# pc_sensything_v1_4.net
KiCad netlist of a schematic drawn in EAGLE
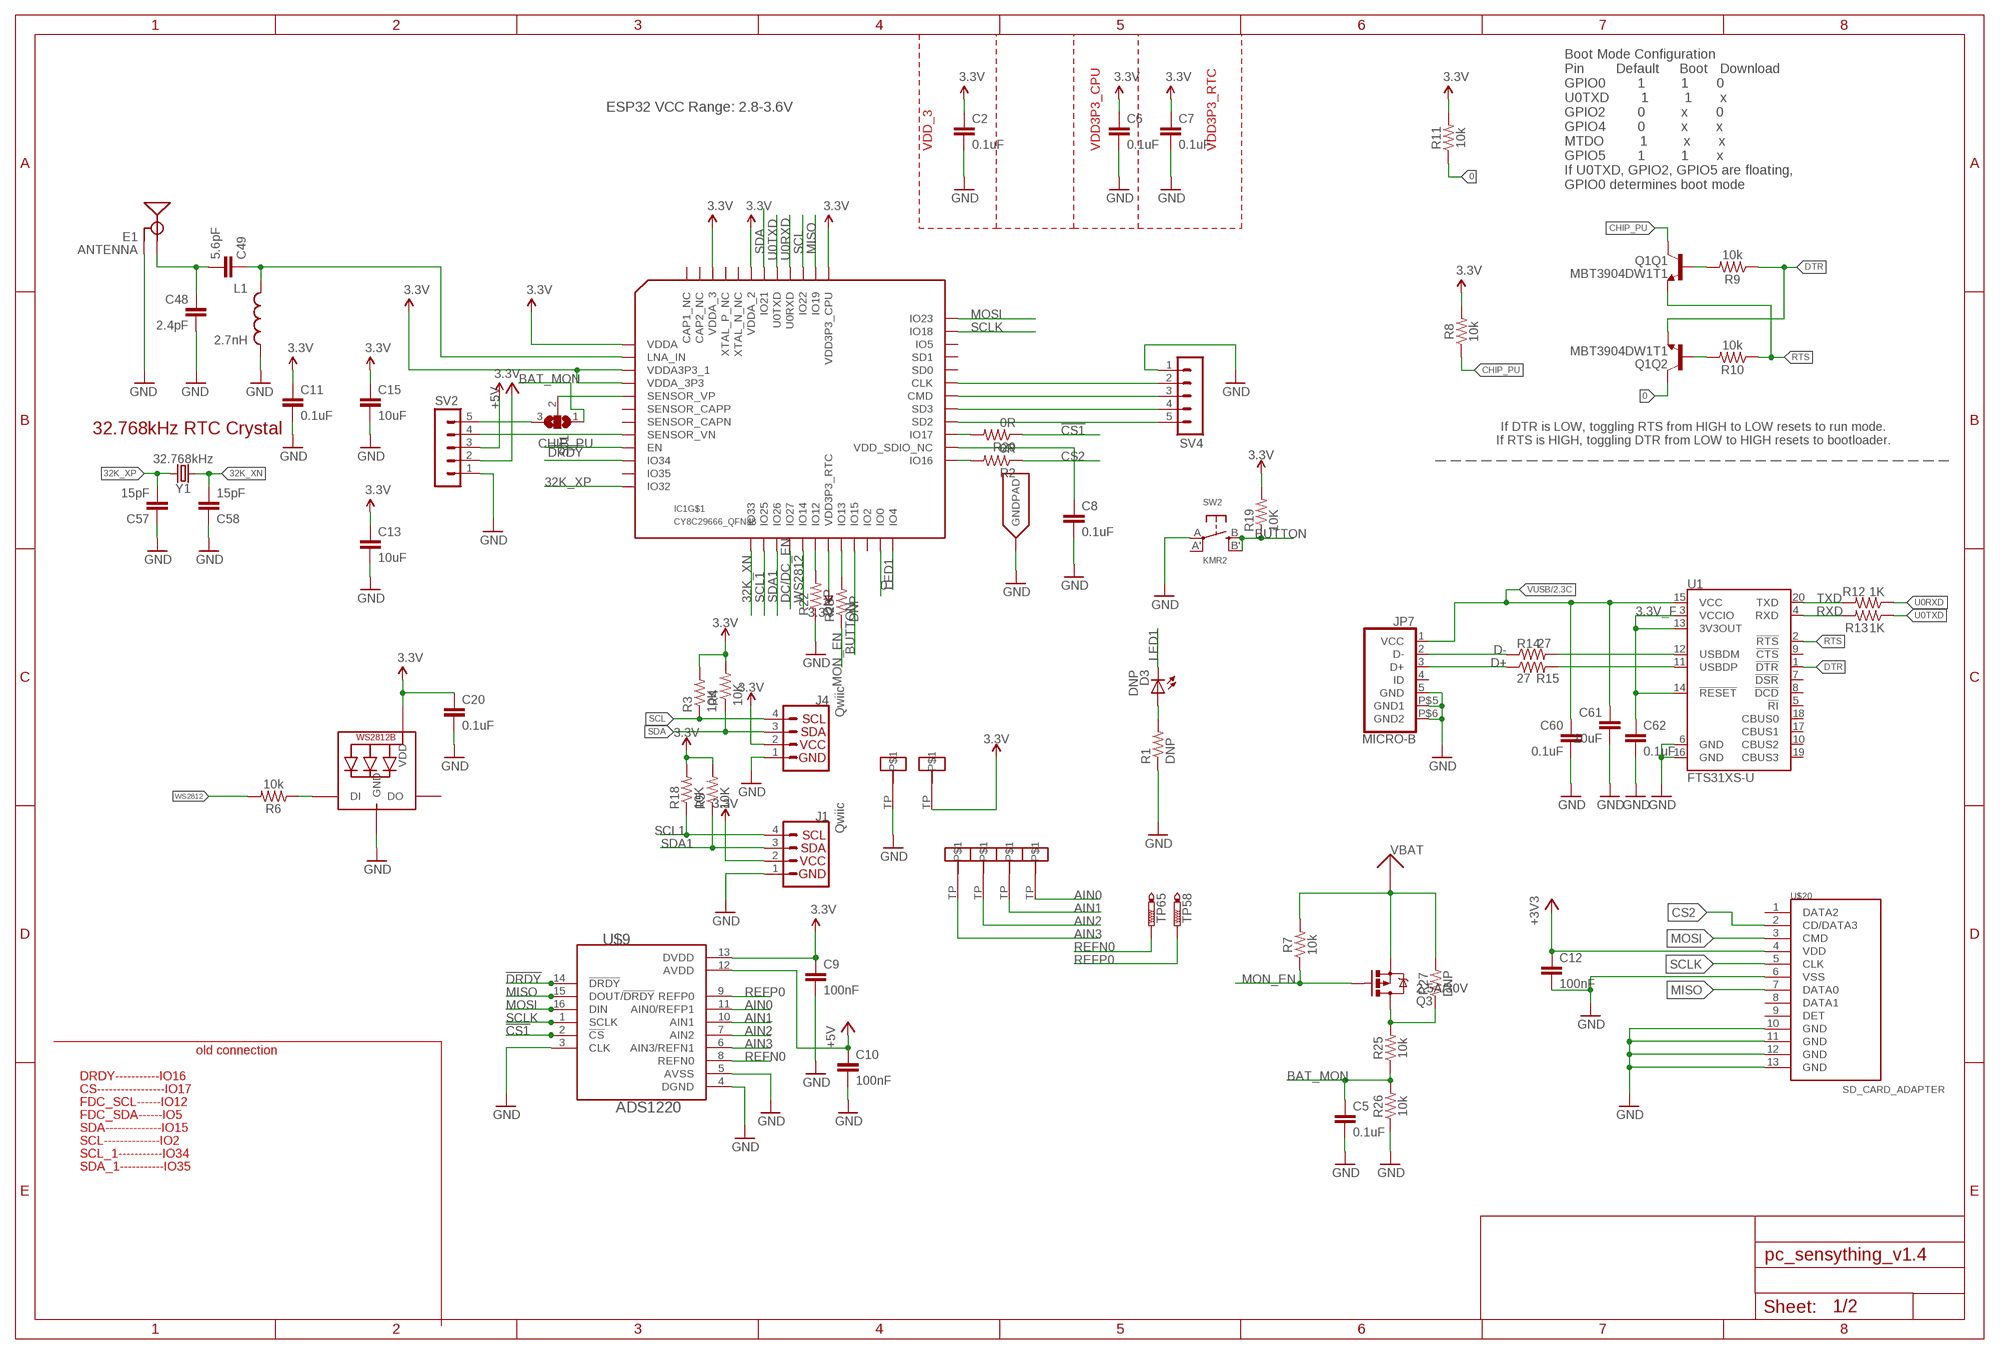
[diagram p0: schematic, sheet 1]
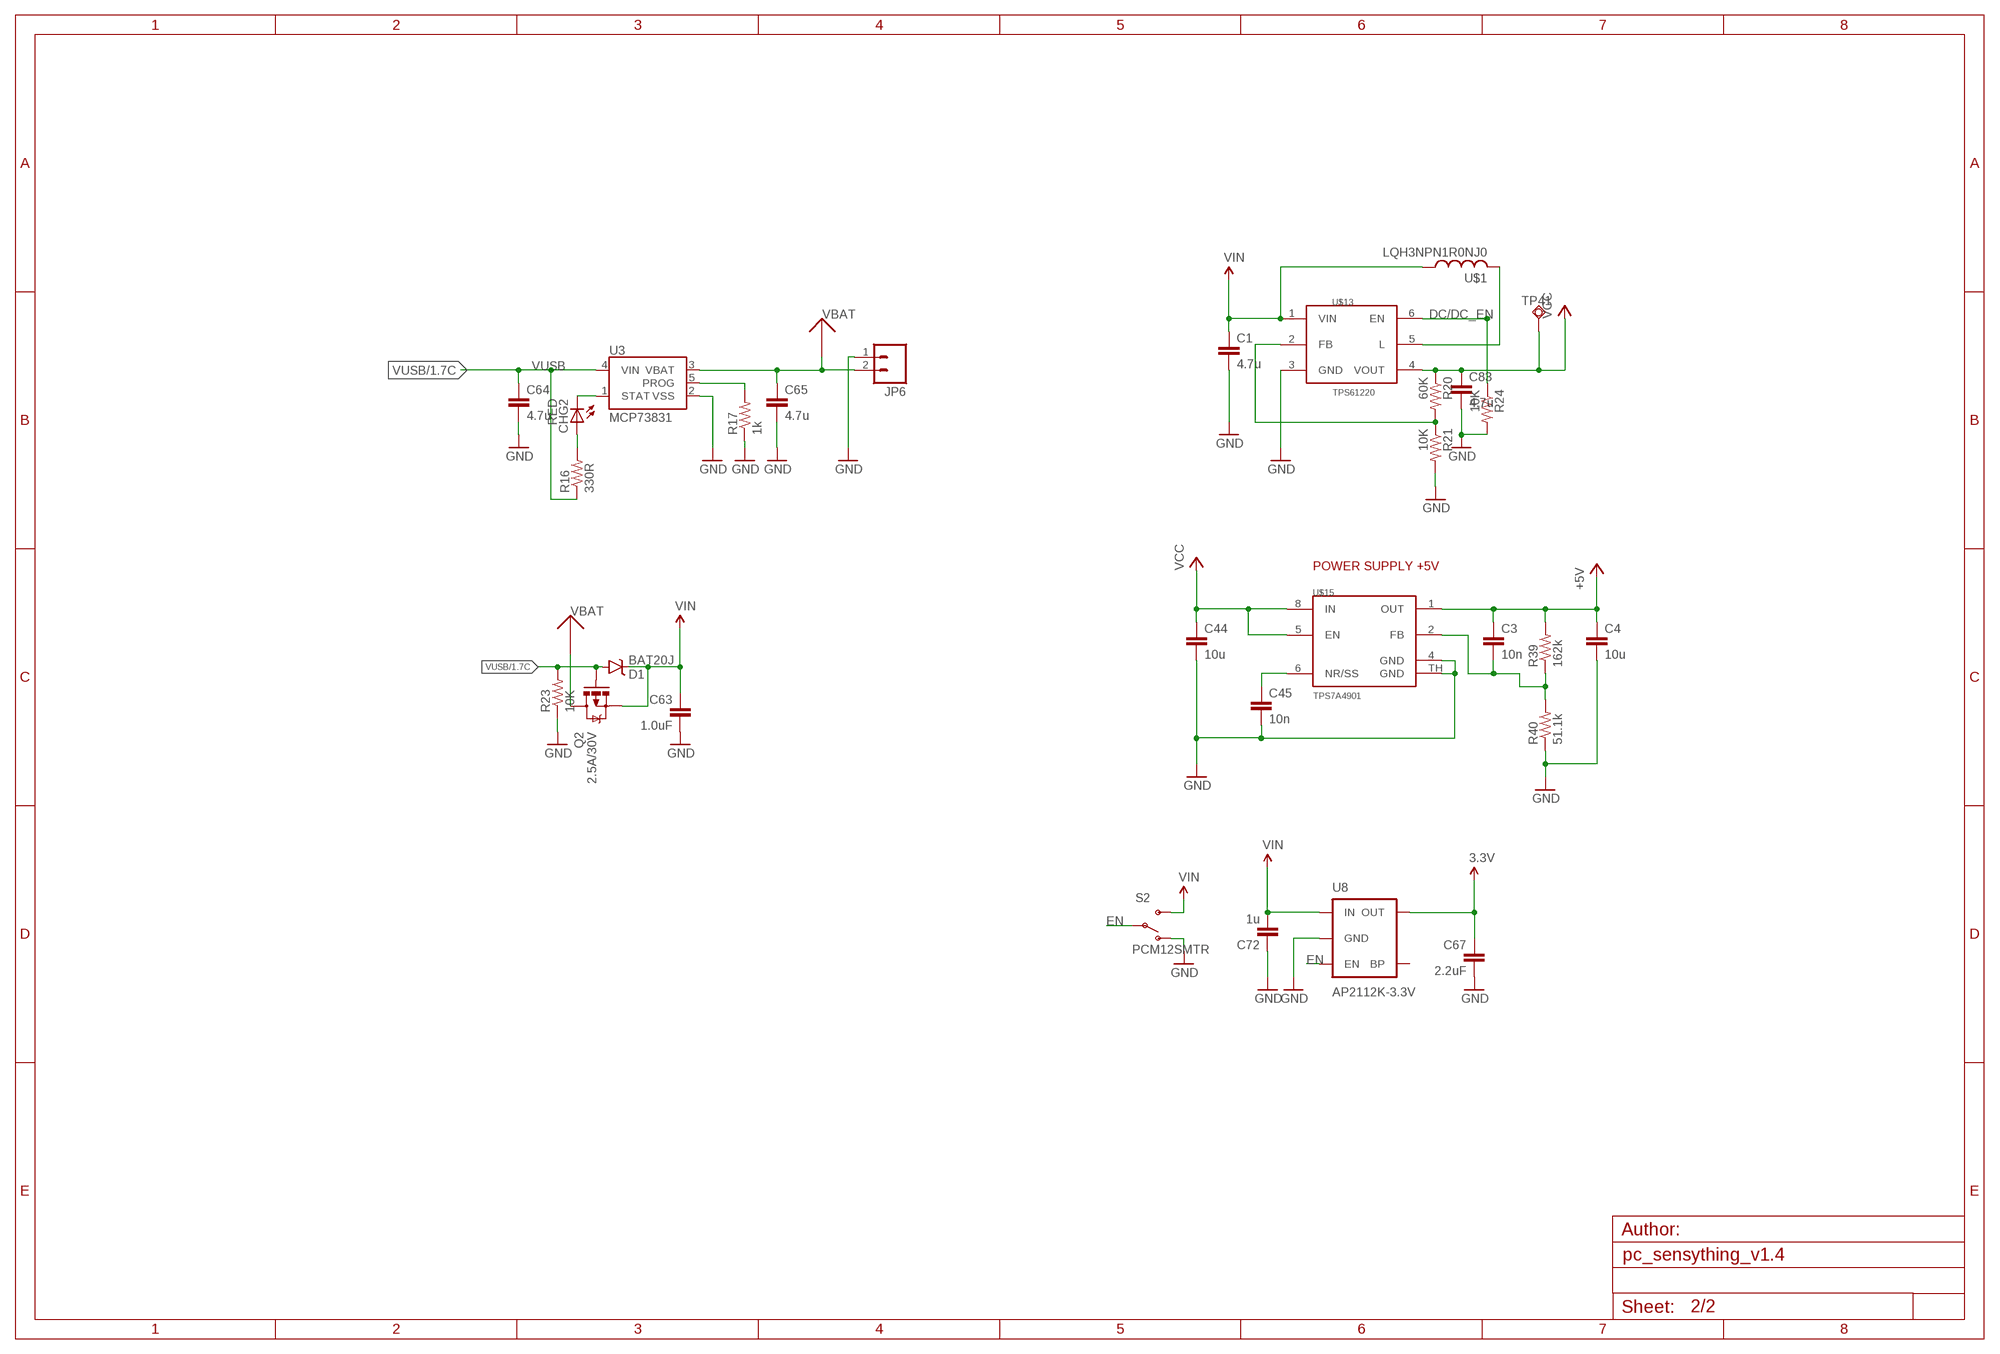
[diagram p1: schematic, sheet 2]

(export (version "E")
  (design (tool "Eeschema 10.0.6"))
  (components
    (comp (ref "C2")
      (value "0.1uF")
      (footprint "eagle-import:0402")
      (libsource (lib "eagle-import") (part "0.1UF-0402-16V-10%"))
    )
    (comp (ref "C5")
      (value "0.1uF")
      (footprint "eagle-import:0402")
      (libsource (lib "eagle-import") (part "0.1UF-0402-16V-10%"))
    )
    (comp (ref "C6")
      (value "0.1uF")
      (footprint "eagle-import:0402")
      (libsource (lib "eagle-import") (part "0.1UF-0402-16V-10%"))
    )
    (comp (ref "C7")
      (value "0.1uF")
      (footprint "eagle-import:0402")
      (libsource (lib "eagle-import") (part "0.1UF-0402-16V-10%"))
    )
    (comp (ref "C8")
      (value "0.1uF")
      (footprint "eagle-import:0402")
      (libsource (lib "eagle-import") (part "0.1UF-0402-16V-10%"))
    )
    (comp (ref "C9")
      (value "100nF")
      (footprint "eagle-import:C0805")
      (libsource (lib "eagle-import") (part "C-EUC0805"))
    )
    (comp (ref "C10")
      (value "100nF")
      (footprint "eagle-import:C0805")
      (libsource (lib "eagle-import") (part "C-EUC0805"))
    )
    (comp (ref "C11")
      (value "0.1uF")
      (footprint "eagle-import:0402")
      (libsource (lib "eagle-import") (part "0.1UF-0402-16V-10%"))
    )
    (comp (ref "C12")
      (value "100nF")
      (footprint "eagle-import:C0402")
      (libsource (lib "eagle-import") (part "C-EUC0402"))
    )
    (comp (ref "C13")
      (value "10uF")
      (footprint "eagle-import:0603")
      (libsource (lib "eagle-import") (part "10UF-0603-6.3V-20%"))
    )
    (comp (ref "C15")
      (value "10uF")
      (footprint "eagle-import:0603")
      (libsource (lib "eagle-import") (part "10UF-0603-6.3V-20%"))
    )
    (comp (ref "C20")
      (value "0.1uF")
      (footprint "eagle-import:0603")
      (libsource (lib "eagle-import") (part "0.1UF-0603-25V-(+80/-20%)"))
    )
    (comp (ref "C48")
      (value "2.4pF")
      (footprint "eagle-import:0603")
      (libsource (lib "eagle-import") (part "2.4PF-0603-50V-5%"))
    )
    (comp (ref "C49")
      (value "5.6pF")
      (footprint "eagle-import:0603")
      (libsource (lib "eagle-import") (part "5.6PF-50V-5%(0603)"))
    )
    (comp (ref "C57")
      (value "15pF")
      (footprint "eagle-import:0603")
      (libsource (lib "eagle-import") (part "15PF-0603-50V-5%"))
    )
    (comp (ref "C58")
      (value "15pF")
      (footprint "eagle-import:0603")
      (libsource (lib "eagle-import") (part "15PF-0603-50V-5%"))
    )
    (comp (ref "C60")
      (value "0.1uF")
      (footprint "eagle-import:C0402")
      (libsource (lib "eagle-import") (part "C-EUC0402"))
    )
    (comp (ref "C61")
      (value "10uF")
      (footprint "eagle-import:C0805")
      (libsource (lib "eagle-import") (part "C-EUC0805"))
    )
    (comp (ref "C62")
      (value "0.1uF")
      (footprint "eagle-import:C0402")
      (libsource (lib "eagle-import") (part "C-EUC0402"))
    )
    (comp (ref "D3")
      (value "DNP")
      (footprint "eagle-import:CHIPLED_0603")
      (libsource (lib "eagle-import") (part "LEDCHIPLED_0603"))
    )
    (comp (ref "E1")
      (value "ANTENNA")
      (footprint "eagle-import:TRACE_ANTENNA_2.4GHZ_25.7MM_TUNED")
      (libsource (lib "eagle-import") (part "ANTENNATRACE-TUNED"))
    )
    (comp (ref "IC1")
      (value "CY8C29666_QFN48")
      (footprint "eagle-import:QFN48")
      (libsource (lib "eagle-import") (part "CY8C29666_QFN48"))
    )
    (comp (ref "J1")
      (value "Qwiic")
      (footprint "eagle-import:1X04_1MM_RA")
      (libsource (lib "eagle-import") (part "QWIIC_CONNECTORJS-1MM"))
    )
    (comp (ref "J4")
      (value "Qwiic")
      (footprint "eagle-import:1X04_1MM_RA")
      (libsource (lib "eagle-import") (part "QWIIC_CONNECTORJS-1MM"))
    )
    (comp (ref "JP7")
      (value "MICRO-B")
      (footprint "eagle-import:MICRO-B")
      (libsource (lib "eagle-import") (part "MICRO-B"))
    )
    (comp (ref "L1")
      (value "2.7nH")
      (footprint "eagle-import:0603")
      (libsource (lib "eagle-import") (part "INDUCTOR0603"))
    )
    (comp (ref "LED1")
      (value "WS2812B5050")
      (footprint "eagle-import:WS2812B")
      (libsource (lib "eagle-import") (part "WS2812B5050"))
    )
    (comp (ref "Q1")
      (value "MBT3904DW1T1")
      (footprint "eagle-import:SC70-6")
      (libsource (lib "eagle-import") (part "MBT3904DW1T1"))
    )
    (comp (ref "Q3")
      (value "2.5A/30V")
      (footprint "eagle-import:SOT23-3")
      (libsource (lib "eagle-import") (part "MOSFET-PCHANNELDMG2307L"))
    )
    (comp (ref "R1")
      (value "DNP")
      (footprint "eagle-import:R0402")
      (libsource (lib "eagle-import") (part "R-US_R0402"))
    )
    (comp (ref "R2")
      (value "0R")
      (footprint "eagle-import:R0402")
      (libsource (lib "eagle-import") (part "R-US_R0402"))
    )
    (comp (ref "R3")
      (value "10K")
      (footprint "eagle-import:R0402")
      (libsource (lib "eagle-import") (part "R-US_R0402"))
    )
    (comp (ref "R4")
      (value "10K")
      (footprint "eagle-import:R0402")
      (libsource (lib "eagle-import") (part "R-US_R0402"))
    )
    (comp (ref "R5")
      (value "10K")
      (footprint "eagle-import:R0402")
      (libsource (lib "eagle-import") (part "R-US_R0402"))
    )
    (comp (ref "R6")
      (value "10k")
      (footprint "eagle-import:0603")
      (libsource (lib "eagle-import") (part "10KOHM-1/10W-1%(0603)0603"))
    )
    (comp (ref "R7")
      (value "10k")
      (footprint "eagle-import:0603")
      (libsource (lib "eagle-import") (part "10KOHM-1/10W-1%(0603)0603"))
    )
    (comp (ref "R8")
      (value "10k")
      (footprint "eagle-import:0603")
      (libsource (lib "eagle-import") (part "10KOHM-1/10W-1%(0603)0603"))
    )
    (comp (ref "R9")
      (value "10k")
      (footprint "eagle-import:0603")
      (libsource (lib "eagle-import") (part "10KOHM-0603-1/10W-1%"))
    )
    (comp (ref "R10")
      (value "10k")
      (footprint "eagle-import:0603")
      (libsource (lib "eagle-import") (part "10KOHM-0603-1/10W-1%"))
    )
    (comp (ref "R11")
      (value "10k")
      (footprint "eagle-import:0603")
      (libsource (lib "eagle-import") (part "10KOHM-1/10W-1%(0603)0603"))
    )
    (comp (ref "R12")
      (value "1K")
      (footprint "eagle-import:R0402")
      (libsource (lib "eagle-import") (part "R-US_R0402"))
    )
    (comp (ref "R13")
      (value "1K")
      (footprint "eagle-import:R0402")
      (libsource (lib "eagle-import") (part "R-US_R0402"))
    )
    (comp (ref "R14")
      (value "27")
      (footprint "eagle-import:R0402")
      (libsource (lib "eagle-import") (part "R-US_R0402"))
    )
    (comp (ref "R15")
      (value "27")
      (footprint "eagle-import:R0402")
      (libsource (lib "eagle-import") (part "R-US_R0402"))
    )
    (comp (ref "R18")
      (value "10K")
      (footprint "eagle-import:R0402")
      (libsource (lib "eagle-import") (part "R-US_R0402"))
    )
    (comp (ref "R19")
      (value "10K")
      (footprint "eagle-import:R0402")
      (libsource (lib "eagle-import") (part "R-US_R0402"))
    )
    (comp (ref "R22")
      (value "DNP")
      (footprint "eagle-import:R0402")
      (libsource (lib "eagle-import") (part "R-US_R0402"))
    )
    (comp (ref "R25")
      (value "10k")
      (footprint "eagle-import:0603")
      (libsource (lib "eagle-import") (part "10KOHM-1/10W-1%(0603)0603"))
    )
    (comp (ref "R26")
      (value "10k")
      (footprint "eagle-import:0603")
      (libsource (lib "eagle-import") (part "10KOHM-1/10W-1%(0603)0603"))
    )
    (comp (ref "R27")
      (value "DNP")
      (footprint "eagle-import:0603")
      (libsource (lib "eagle-import") (part "10KOHM-1/10W-1%(0603)0603"))
    )
    (comp (ref "R28")
      (value "DNP")
      (footprint "eagle-import:R0402")
      (libsource (lib "eagle-import") (part "R-US_R0402"))
    )
    (comp (ref "R29")
      (value "0R")
      (footprint "eagle-import:R0402")
      (libsource (lib "eagle-import") (part "R-US_R0402"))
    )
    (comp (ref "SJ1")
      (value "SJ2W")
      (footprint "eagle-import:SJ_2")
      (libsource (lib "eagle-import") (part "SJ2W"))
    )
    (comp (ref "SV2")
      (value "MA05-1")
      (footprint "eagle-import:MA05-1")
      (libsource (lib "eagle-import") (part "MA05-1"))
    )
    (comp (ref "SV4")
      (value "MA05-1")
      (footprint "eagle-import:MA05-1")
      (libsource (lib "eagle-import") (part "MA05-1"))
    )
    (comp (ref "SW2")
      (value "KMR2")
      (footprint "eagle-import:BTN_KMR2_4.6X2.8")
      (libsource (lib "eagle-import") (part "SWITCH_TACT_SMT4.6X2.8"))
    )
    (comp (ref "TP58")
      (value "PTR1PAD1-13")
      (footprint "eagle-import:P1-13")
      (libsource (lib "eagle-import") (part "PTR1PAD1-13"))
    )
    (comp (ref "TP65")
      (value "PTR1PAD1-13")
      (footprint "eagle-import:P1-13")
      (libsource (lib "eagle-import") (part "PTR1PAD1-13"))
    )
    (comp (ref "U$3")
      (value "SENSYTHING_CON")
      (footprint "eagle-import:SENSYTHING_CON")
      (libsource (lib "eagle-import") (part "SENSYTHING_CON"))
    )
    (comp (ref "U$7")
      (value "SENSYTHING_CON")
      (footprint "eagle-import:SENSYTHING_CON")
      (libsource (lib "eagle-import") (part "SENSYTHING_CON"))
    )
    (comp (ref "U$8")
      (value "SENSYTHING_CON")
      (footprint "eagle-import:SENSYTHING_CON")
      (libsource (lib "eagle-import") (part "SENSYTHING_CON"))
    )
    (comp (ref "U$9")
      (value "ADS1220")
      (footprint "eagle-import:TSSOP-16")
      (libsource (lib "eagle-import") (part "ADS1220"))
    )
    (comp (ref "U$11")
      (value "SENSYTHING_CON")
      (footprint "eagle-import:SENSYTHING_CON")
      (libsource (lib "eagle-import") (part "SENSYTHING_CON"))
    )
    (comp (ref "U$12")
      (value "SENSYTHING_CON")
      (footprint "eagle-import:SENSYTHING_CON")
      (libsource (lib "eagle-import") (part "SENSYTHING_CON"))
    )
    (comp (ref "U$14")
      (value "SENSYTHING_CON")
      (footprint "eagle-import:SENSYTHING_CON")
      (libsource (lib "eagle-import") (part "SENSYTHING_CON"))
    )
    (comp (ref "U$20")
      (value "SD_CARD_ADAPTER")
      (footprint "eagle-import:SD-105162")
      (libsource (lib "eagle-import") (part "SD_CARD_ADAPTER"))
    )
    (comp (ref "U1")
      (value "FTS31XS-U")
      (footprint "eagle-import:SSOP20_L")
      (libsource (lib "eagle-import") (part "FT231XS"))
    )
    (comp (ref "Y1")
      (value "32.768kHz")
      (footprint "eagle-import:CRYSTAL-SMD-3.2X1.5MM")
      (libsource (lib "eagle-import") (part "CRYSTAL-32.768KHZSMD-3.2X1.5"))
    )
    (comp (ref "C1")
      (value "4.7u")
      (footprint "eagle-import:C0805")
      (libsource (lib "eagle-import") (part "C-EUC0805"))
    )
    (comp (ref "C3")
      (value "10n")
      (footprint "eagle-import:C0402")
      (libsource (lib "eagle-import") (part "C-EUC0402"))
    )
    (comp (ref "C4")
      (value "10u")
      (footprint "eagle-import:C0805")
      (libsource (lib "eagle-import") (part "C-EUC0805"))
    )
    (comp (ref "C44")
      (value "10u")
      (footprint "eagle-import:C0805")
      (libsource (lib "eagle-import") (part "C-EUC0805"))
    )
    (comp (ref "C45")
      (value "10n")
      (footprint "eagle-import:C0402")
      (libsource (lib "eagle-import") (part "C-EUC0402"))
    )
    (comp (ref "C63")
      (value "1.0uF")
      (footprint "eagle-import:C0402")
      (libsource (lib "eagle-import") (part "C-EUC0402"))
    )
    (comp (ref "C64")
      (value "4.7u")
      (footprint "eagle-import:C0805")
      (libsource (lib "eagle-import") (part "C-EUC0805"))
    )
    (comp (ref "C65")
      (value "4.7u")
      (footprint "eagle-import:C0805")
      (libsource (lib "eagle-import") (part "C-EUC0805"))
    )
    (comp (ref "C67")
      (value "2.2uF")
      (footprint "eagle-import:C0402")
      (libsource (lib "eagle-import") (part "C-EUC0402"))
    )
    (comp (ref "C72")
      (value "1u")
      (footprint "eagle-import:C0402")
      (libsource (lib "eagle-import") (part "C-EUC0402"))
    )
    (comp (ref "C83")
      (value "4.7u")
      (footprint "eagle-import:C0805")
      (libsource (lib "eagle-import") (part "C-EUC0805"))
    )
    (comp (ref "CHG2")
      (value "RED")
      (footprint "eagle-import:CHIPLED_0603")
      (libsource (lib "eagle-import") (part "LEDCHIPLED_0603"))
    )
    (comp (ref "D1")
      (value "BAT20J")
      (footprint "eagle-import:SOD-323")
      (libsource (lib "eagle-import") (part "DIODE-SCHOTTKY-BAT20J"))
    )
    (comp (ref "JP6")
      (value "M02-JST-2MM-SMT")
      (footprint "eagle-import:JST-2-SMD")
      (libsource (lib "eagle-import") (part "M02-JST-2MM-SMT"))
    )
    (comp (ref "Q2")
      (value "2.5A/30V")
      (footprint "eagle-import:SOT23-3")
      (libsource (lib "eagle-import") (part "MOSFET-PCHANNELDMG2307L"))
    )
    (comp (ref "R16")
      (value "330R")
      (footprint "eagle-import:R0402")
      (libsource (lib "eagle-import") (part "R-US_R0402"))
    )
    (comp (ref "R17")
      (value "1k")
      (footprint "eagle-import:R0402")
      (libsource (lib "eagle-import") (part "R-US_R0402"))
    )
    (comp (ref "R20")
      (value "60K")
      (footprint "eagle-import:R0805")
      (libsource (lib "eagle-import") (part "R-US_R0805"))
    )
    (comp (ref "R21")
      (value "10K")
      (footprint "eagle-import:R0805")
      (libsource (lib "eagle-import") (part "R-US_R0805"))
    )
    (comp (ref "R23")
      (value "10K")
      (footprint "eagle-import:R0402")
      (libsource (lib "eagle-import") (part "R-US_R0402"))
    )
    (comp (ref "R24")
      (value "10K")
      (footprint "eagle-import:R0402")
      (libsource (lib "eagle-import") (part "R-US_R0402"))
    )
    (comp (ref "R39")
      (value "162k")
      (footprint "eagle-import:R0805")
      (libsource (lib "eagle-import") (part "R-US_R0805"))
    )
    (comp (ref "R40")
      (value "51.1k")
      (footprint "eagle-import:R0805")
      (libsource (lib "eagle-import") (part "R-US_R0805"))
    )
    (comp (ref "S2")
      (value "PCM12SMTR")
      (footprint "eagle-import:SWITCH-SPST-SMD-A")
      (libsource (lib "eagle-import") (part "SWITCH-SPDT-SMD-A"))
    )
    (comp (ref "TP41")
      (value "TPSQB1,27")
      (footprint "eagle-import:B1,27")
      (libsource (lib "eagle-import") (part "TPSQB1,27"))
    )
    (comp (ref "U$1")
      (value "LQH3NPN1R0NJ0")
      (footprint "eagle-import:LQH3NP")
      (libsource (lib "eagle-import") (part "LQH3NPN1R0NJ0"))
    )
    (comp (ref "U$13")
      (value "TPS61220")
      (footprint "eagle-import:SC-70-6")
      (libsource (lib "eagle-import") (part "TPS61222"))
    )
    (comp (ref "U$15")
      (value "TPS7A4901")
      (footprint "eagle-import:S-PDSO-G08")
      (libsource (lib "eagle-import") (part "TPS7A4901"))
    )
    (comp (ref "U3")
      (value "MCP73831")
      (footprint "eagle-import:SOT23-5")
      (libsource (lib "eagle-import") (part "MCP73831"))
    )
    (comp (ref "U8")
      (value "AP2112K-3.3V")
      (footprint "eagle-import:SOT23-5")
      (libsource (lib "eagle-import") (part "V_REG_LDOSMD"))
    )
  )
  (nets
    (net (code "1") (name "+3V3") (class "Default")
      (node (ref "C12") (pin "1") (pinfunction "1_1") (pintype "passive"))
      (node (ref "U$20") (pin "4") (pinfunction "VDD_4") (pintype "bidirectional"))
    )
    (net (code "2") (name "+5V") (class "Default")
      (node (ref "C10") (pin "1") (pinfunction "1_1") (pintype "passive"))
      (node (ref "C3") (pin "1") (pinfunction "1_1") (pintype "passive"))
      (node (ref "C4") (pin "1") (pinfunction "1_1") (pintype "passive"))
      (node (ref "R39") (pin "2") (pinfunction "2_2") (pintype "passive"))
      (node (ref "SV2") (pin "2") (pinfunction "2_2") (pintype "passive"))
      (node (ref "U$15") (pin "1") (pinfunction "OUT_1") (pintype "bidirectional"))
      (node (ref "U$9") (pin "12") (pinfunction "AVDD_12") (pintype "bidirectional"))
    )
    (net (code "3") (name "0") (class "Default")
      (node (ref "IC1") (pin "23") (pinfunction "IO0_23") (pintype "bidirectional"))
      (node (ref "Q1") (pin "6") (pinfunction "C_6") (pintype "passive"))
      (node (ref "R11") (pin "1") (pinfunction "1_1") (pintype "passive"))
    )
    (net (code "4") (name "3.3V") (class "Default")
      (node (ref "C11") (pin "1") (pinfunction "1_1") (pintype "passive"))
      (node (ref "C13") (pin "1") (pinfunction "1_1") (pintype "passive"))
      (node (ref "C15") (pin "1") (pinfunction "1_1") (pintype "passive"))
      (node (ref "C2") (pin "1") (pinfunction "1_1") (pintype "passive"))
      (node (ref "C20") (pin "1") (pinfunction "1_1") (pintype "passive"))
      (node (ref "C6") (pin "1") (pinfunction "1_1") (pintype "passive"))
      (node (ref "C67") (pin "1") (pinfunction "1_1") (pintype "passive"))
      (node (ref "C7") (pin "1") (pinfunction "1_1") (pintype "passive"))
      (node (ref "C9") (pin "1") (pinfunction "1_1") (pintype "passive"))
      (node (ref "IC1") (pin "1") (pinfunction "VDDA_1") (pintype "bidirectional"))
      (node (ref "IC1") (pin "19") (pinfunction "VDD3P3_RTC_19") (pintype "bidirectional"))
      (node (ref "IC1") (pin "3") (pinfunction "VDDA3P3_1_3") (pintype "bidirectional"))
      (node (ref "IC1") (pin "37") (pinfunction "VDD3P3_CPU_37") (pintype "bidirectional"))
      (node (ref "IC1") (pin "4") (pinfunction "VDDA_3P3_4") (pintype "bidirectional"))
      (node (ref "IC1") (pin "43") (pinfunction "VDDA_2_43") (pintype "bidirectional"))
      (node (ref "IC1") (pin "46") (pinfunction "VDDA_3_46") (pintype "bidirectional"))
      (node (ref "J1") (pin "2") (pinfunction "2_2") (pintype "power_in"))
      (node (ref "J4") (pin "2") (pinfunction "2_2") (pintype "power_in"))
      (node (ref "LED1") (pin "1-VDD") (pinfunction "VDD_1-VDD") (pintype "power_in"))
      (node (ref "R11") (pin "2") (pinfunction "2_2") (pintype "passive"))
      (node (ref "R18") (pin "2") (pinfunction "2_2") (pintype "passive"))
      (node (ref "R19") (pin "2") (pinfunction "2_2") (pintype "passive"))
      (node (ref "R3") (pin "2") (pinfunction "2_2") (pintype "passive"))
      (node (ref "R4") (pin "2") (pinfunction "2_2") (pintype "passive"))
      (node (ref "R5") (pin "2") (pinfunction "2_2") (pintype "passive"))
      (node (ref "R8") (pin "2") (pinfunction "2_2") (pintype "passive"))
      (node (ref "SV2") (pin "3") (pinfunction "3_3") (pintype "passive"))
      (node (ref "U$14") (pin "TP") (pinfunction "P$1_TP") (pintype "bidirectional"))
      (node (ref "U$9") (pin "13") (pinfunction "DVDD_13") (pintype "bidirectional"))
      (node (ref "U8") (pin "5") (pinfunction "OUT_5") (pintype "passive"))
    )
    (net (code "5") (name "3.3V_F") (class "Default")
      (node (ref "C62") (pin "1") (pinfunction "1_1") (pintype "passive"))
      (node (ref "U1") (pin "13") (pinfunction "3V3OUT_13") (pintype "bidirectional"))
      (node (ref "U1") (pin "14") (pinfunction "~{RESET}_14") (pintype "bidirectional"))
      (node (ref "U1") (pin "3") (pinfunction "VCCIO_3") (pintype "bidirectional"))
    )
    (net (code "6") (name "32K_XN") (class "Default")
      (node (ref "C58") (pin "2") (pinfunction "2_2") (pintype "passive"))
      (node (ref "IC1") (pin "13") (pinfunction "IO33_13") (pintype "bidirectional"))
      (node (ref "Y1") (pin "P$2") (pinfunction "2_P$2") (pintype "passive"))
    )
    (net (code "7") (name "32K_XP") (class "Default")
      (node (ref "C57") (pin "2") (pinfunction "2_2") (pintype "passive"))
      (node (ref "IC1") (pin "12") (pinfunction "IO32_12") (pintype "bidirectional"))
      (node (ref "Y1") (pin "P$1") (pinfunction "1_P$1") (pintype "passive"))
    )
    (net (code "8") (name "AIN0") (class "Default")
      (node (ref "U$11") (pin "TP") (pinfunction "P$1_TP") (pintype "bidirectional"))
      (node (ref "U$9") (pin "11") (pinfunction "AIN0/REFP1_11") (pintype "bidirectional"))
    )
    (net (code "9") (name "AIN1") (class "Default")
      (node (ref "U$8") (pin "TP") (pinfunction "P$1_TP") (pintype "bidirectional"))
      (node (ref "U$9") (pin "10") (pinfunction "AIN1_10") (pintype "bidirectional"))
    )
    (net (code "10") (name "AIN2") (class "Default")
      (node (ref "U$7") (pin "TP") (pinfunction "P$1_TP") (pintype "bidirectional"))
      (node (ref "U$9") (pin "7") (pinfunction "AIN2_7") (pintype "bidirectional"))
    )
    (net (code "11") (name "AIN3") (class "Default")
      (node (ref "U$3") (pin "TP") (pinfunction "P$1_TP") (pintype "bidirectional"))
      (node (ref "U$9") (pin "6") (pinfunction "AIN3/REFN1_6") (pintype "bidirectional"))
    )
    (net (code "12") (name "BAT_MON") (class "Default")
      (node (ref "C5") (pin "1") (pinfunction "1_1") (pintype "passive"))
      (node (ref "R25") (pin "1") (pinfunction "1_1") (pintype "passive"))
      (node (ref "R26") (pin "2") (pinfunction "2_2") (pintype "passive"))
      (node (ref "SJ1") (pin "1") (pinfunction "1_1") (pintype "passive"))
    )
    (net (code "13") (name "BUTTON") (class "Default")
      (node (ref "IC1") (pin "21") (pinfunction "IO15_21") (pintype "bidirectional"))
      (node (ref "R19") (pin "1") (pinfunction "1_1") (pintype "passive"))
      (node (ref "SW2") (pin "B") (pinfunction "S_B") (pintype "passive"))
      (node (ref "SW2") (pin "B'") (pinfunction "S1_B'") (pintype "passive"))
    )
    (net (code "14") (name "CHIP_PU") (class "Default")
      (node (ref "IC1") (pin "9") (pinfunction "EN_9") (pintype "bidirectional"))
      (node (ref "Q1") (pin "3") (pinfunction "C_3") (pintype "passive"))
      (node (ref "R8") (pin "1") (pinfunction "1_1") (pintype "passive"))
    )
    (net (code "15") (name "CS2") (class "Default")
      (node (ref "R2") (pin "1") (pinfunction "1_1") (pintype "passive"))
      (node (ref "U$20") (pin "2") (pinfunction "CD/DATA3_2") (pintype "bidirectional"))
    )
    (net (code "16") (name "D+") (class "Default")
      (node (ref "JP7") (pin "3") (pinfunction "D+_3") (pintype "bidirectional"))
      (node (ref "R15") (pin "1") (pinfunction "1_1") (pintype "passive"))
    )
    (net (code "17") (name "D-") (class "Default")
      (node (ref "JP7") (pin "2") (pinfunction "D-_2") (pintype "bidirectional"))
      (node (ref "R14") (pin "1") (pinfunction "1_1") (pintype "passive"))
    )
    (net (code "18") (name "DC{slash}DC_EN") (class "Default")
      (node (ref "IC1") (pin "16") (pinfunction "IO27_16") (pintype "bidirectional"))
      (node (ref "R24") (pin "1") (pinfunction "1_1") (pintype "passive"))
      (node (ref "U$13") (pin "6") (pinfunction "EN_6") (pintype "bidirectional"))
    )
    (net (code "19") (name "DTR") (class "Default")
      (node (ref "Q1") (pin "1") (pinfunction "E_1") (pintype "passive"))
      (node (ref "R9") (pin "1") (pinfunction "1_1") (pintype "passive"))
      (node (ref "U1") (pin "1") (pinfunction "~{DTR}_1") (pintype "bidirectional"))
    )
    (net (code "20") (name "EN") (class "Default")
      (node (ref "S2") (pin "2") (pinfunction "P_2") (pintype "passive"))
      (node (ref "U8") (pin "3") (pinfunction "EN_3") (pintype "input"))
    )
    (net (code "21") (name "GND") (class "Default")
      (node (ref "C1") (pin "2") (pinfunction "2_2") (pintype "passive"))
      (node (ref "C10") (pin "2") (pinfunction "2_2") (pintype "passive"))
      (node (ref "C11") (pin "2") (pinfunction "2_2") (pintype "passive"))
      (node (ref "C12") (pin "2") (pinfunction "2_2") (pintype "passive"))
      (node (ref "C13") (pin "2") (pinfunction "2_2") (pintype "passive"))
      (node (ref "C15") (pin "2") (pinfunction "2_2") (pintype "passive"))
      (node (ref "C2") (pin "2") (pinfunction "2_2") (pintype "passive"))
      (node (ref "C20") (pin "2") (pinfunction "2_2") (pintype "passive"))
      (node (ref "C4") (pin "2") (pinfunction "2_2") (pintype "passive"))
      (node (ref "C44") (pin "2") (pinfunction "2_2") (pintype "passive"))
      (node (ref "C45") (pin "2") (pinfunction "2_2") (pintype "passive"))
      (node (ref "C48") (pin "2") (pinfunction "2_2") (pintype "passive"))
      (node (ref "C5") (pin "2") (pinfunction "2_2") (pintype "passive"))
      (node (ref "C57") (pin "1") (pinfunction "1_1") (pintype "passive"))
      (node (ref "C58") (pin "1") (pinfunction "1_1") (pintype "passive"))
      (node (ref "C6") (pin "2") (pinfunction "2_2") (pintype "passive"))
      (node (ref "C60") (pin "2") (pinfunction "2_2") (pintype "passive"))
      (node (ref "C61") (pin "2") (pinfunction "2_2") (pintype "passive"))
      (node (ref "C62") (pin "2") (pinfunction "2_2") (pintype "passive"))
      (node (ref "C63") (pin "2") (pinfunction "2_2") (pintype "passive"))
      (node (ref "C64") (pin "2") (pinfunction "2_2") (pintype "passive"))
      (node (ref "C65") (pin "2") (pinfunction "2_2") (pintype "passive"))
      (node (ref "C67") (pin "2") (pinfunction "2_2") (pintype "passive"))
      (node (ref "C7") (pin "2") (pinfunction "2_2") (pintype "passive"))
      (node (ref "C72") (pin "1") (pinfunction "1_1") (pintype "passive"))
      (node (ref "C8") (pin "2") (pinfunction "2_2") (pintype "passive"))
      (node (ref "C83") (pin "2") (pinfunction "2_2") (pintype "passive"))
      (node (ref "C9") (pin "2") (pinfunction "2_2") (pintype "passive"))
      (node (ref "E1") (pin "GND") (pinfunction "GND_GND") (pintype "bidirectional"))
      (node (ref "E1") (pin "GND2") (pinfunction "GND_GND2") (pintype "bidirectional"))
      (node (ref "IC1") (pin "EXP") (pinfunction "GNDPAD_EXP") (pintype "power_in"))
      (node (ref "J1") (pin "1") (pinfunction "1_1") (pintype "power_in"))
      (node (ref "J4") (pin "1") (pinfunction "1_1") (pintype "power_in"))
      (node (ref "JP6") (pin "1") (pinfunction "1_1") (pintype "passive"))
      (node (ref "JP7") (pin "5") (pinfunction "GND_5") (pintype "bidirectional"))
      (node (ref "JP7") (pin "P$5") (pinfunction "GND1_P$5") (pintype "bidirectional"))
      (node (ref "JP7") (pin "P$6") (pinfunction "GND2_P$6") (pintype "bidirectional"))
      (node (ref "L1") (pin "2") (pinfunction "2_2") (pintype "passive"))
      (node (ref "LED1") (pin "3-GND") (pinfunction "GND_3-GND") (pintype "power_in"))
      (node (ref "R1") (pin "1") (pinfunction "1_1") (pintype "passive"))
      (node (ref "R17") (pin "1") (pinfunction "1_1") (pintype "passive"))
      (node (ref "R21") (pin "2") (pinfunction "2_2") (pintype "passive"))
      (node (ref "R22") (pin "1") (pinfunction "1_1") (pintype "passive"))
      (node (ref "R23") (pin "1") (pinfunction "1_1") (pintype "passive"))
      (node (ref "R24") (pin "2") (pinfunction "2_2") (pintype "passive"))
      (node (ref "R26") (pin "1") (pinfunction "1_1") (pintype "passive"))
      (node (ref "R40") (pin "1") (pinfunction "1_1") (pintype "passive"))
      (node (ref "S2") (pin "1") (pinfunction "O_1") (pintype "passive"))
      (node (ref "SV2") (pin "1") (pinfunction "1_1") (pintype "passive"))
      (node (ref "SV4") (pin "1") (pinfunction "1_1") (pintype "passive"))
      (node (ref "SW2") (pin "A") (pinfunction "P_A") (pintype "passive"))
      (node (ref "U$12") (pin "TP") (pinfunction "P$1_TP") (pintype "bidirectional"))
      (node (ref "U$13") (pin "3") (pinfunction "GND_3") (pintype "bidirectional"))
      (node (ref "U$15") (pin "4") (pinfunction "GND_4") (pintype "bidirectional"))
      (node (ref "U$15") (pin "TH") (pinfunction "GND_TH") (pintype "bidirectional"))
      (node (ref "U$20") (pin "10") (pinfunction "GND_10") (pintype "bidirectional"))
      (node (ref "U$20") (pin "11") (pinfunction "GND_11") (pintype "bidirectional"))
      (node (ref "U$20") (pin "12") (pinfunction "GND_12") (pintype "bidirectional"))
      (node (ref "U$20") (pin "13") (pinfunction "GND_13") (pintype "bidirectional"))
      (node (ref "U$20") (pin "6") (pinfunction "VSS_6") (pintype "bidirectional"))
      (node (ref "U$9") (pin "3") (pinfunction "CLK_3") (pintype "bidirectional"))
      (node (ref "U$9") (pin "4") (pinfunction "DGND_4") (pintype "bidirectional"))
      (node (ref "U$9") (pin "5") (pinfunction "AVSS_5") (pintype "bidirectional"))
      (node (ref "U1") (pin "16") (pinfunction "GND_16") (pintype "bidirectional"))
      (node (ref "U1") (pin "6") (pinfunction "GND_6") (pintype "bidirectional"))
      (node (ref "U3") (pin "2") (pinfunction "VSS_2") (pintype "power_in"))
      (node (ref "U8") (pin "2") (pinfunction "GND_2") (pintype "input"))
    )
    (net (code "22") (name "LED1") (class "Default")
      (node (ref "D3") (pin "C") (pinfunction "C_C") (pintype "passive"))
      (node (ref "IC1") (pin "24") (pinfunction "IO4_24") (pintype "bidirectional"))
    )
    (net (code "23") (name "MISO") (class "Default")
      (node (ref "IC1") (pin "38") (pinfunction "IO19_38") (pintype "bidirectional"))
      (node (ref "U$20") (pin "7") (pinfunction "DATA0_7") (pintype "bidirectional"))
      (node (ref "U$9") (pin "15") (pinfunction "DOUT/~{DRDY}_15") (pintype "bidirectional"))
    )
    (net (code "24") (name "MON_EN") (class "Default")
      (node (ref "Q3") (pin "1") (pinfunction "G_1") (pintype "passive"))
      (node (ref "R28") (pin "1") (pinfunction "1_1") (pintype "passive"))
      (node (ref "R7") (pin "1") (pinfunction "1_1") (pintype "passive"))
    )
    (net (code "25") (name "MOSI") (class "Default")
      (node (ref "IC1") (pin "36") (pinfunction "IO23_36") (pintype "bidirectional"))
      (node (ref "U$20") (pin "3") (pinfunction "CMD_3") (pintype "bidirectional"))
      (node (ref "U$9") (pin "16") (pinfunction "DIN_16") (pintype "bidirectional"))
    )
    (net (code "26") (name "Net-(CHG2-PadA)") (class "Default")
      (node (ref "CHG2") (pin "A") (pinfunction "A_A") (pintype "passive"))
      (node (ref "R16") (pin "2") (pinfunction "2_2") (pintype "passive"))
    )
    (net (code "27") (name "Net-(D3-PadA)") (class "Default")
      (node (ref "D3") (pin "A") (pinfunction "A_A") (pintype "passive"))
      (node (ref "R1") (pin "2") (pinfunction "2_2") (pintype "passive"))
    )
    (net (code "28") (name "Net-(E1-SIGNAL)") (class "Default")
      (node (ref "C48") (pin "1") (pinfunction "1_1") (pintype "passive"))
      (node (ref "C49") (pin "2") (pinfunction "2_2") (pintype "passive"))
      (node (ref "E1") (pin "ANT") (pinfunction "SIGNAL_ANT") (pintype "bidirectional"))
    )
    (net (code "29") (name "Net-(IC1A-CLK)") (class "Default")
      (node (ref "IC1") (pin "31") (pinfunction "CLK_31") (pintype "bidirectional"))
      (node (ref "SV4") (pin "2") (pinfunction "2_2") (pintype "passive"))
    )
    (net (code "30") (name "Net-(IC1A-CMD)") (class "Default")
      (node (ref "IC1") (pin "30") (pinfunction "CMD_30") (pintype "bidirectional"))
      (node (ref "SV4") (pin "3") (pinfunction "3_3") (pintype "passive"))
    )
    (net (code "31") (name "Net-(IC1A-IO12)") (class "Default")
      (node (ref "IC1") (pin "18") (pinfunction "IO12_18") (pintype "power_in"))
      (node (ref "R22") (pin "2") (pinfunction "2_2") (pintype "passive"))
    )
    (net (code "32") (name "Net-(IC1A-IO13)") (class "Default")
      (node (ref "IC1") (pin "20") (pinfunction "IO13_20") (pintype "bidirectional"))
      (node (ref "R28") (pin "2") (pinfunction "2_2") (pintype "passive"))
    )
    (net (code "33") (name "Net-(IC1A-IO16)") (class "Default")
      (node (ref "IC1") (pin "25") (pinfunction "IO16_25") (pintype "bidirectional"))
      (node (ref "R2") (pin "2") (pinfunction "2_2") (pintype "passive"))
    )
    (net (code "34") (name "Net-(IC1A-IO17)") (class "Default")
      (node (ref "IC1") (pin "27") (pinfunction "IO17_27") (pintype "bidirectional"))
      (node (ref "R29") (pin "2") (pinfunction "2_2") (pintype "passive"))
    )
    (net (code "35") (name "Net-(IC1A-LNA_IN)") (class "Default")
      (node (ref "C49") (pin "1") (pinfunction "1_1") (pintype "passive"))
      (node (ref "IC1") (pin "2") (pinfunction "LNA_IN_2") (pintype "bidirectional"))
      (node (ref "L1") (pin "1") (pinfunction "1_1") (pintype "passive"))
    )
    (net (code "36") (name "Net-(IC1A-SD2)") (class "Default")
      (node (ref "IC1") (pin "28") (pinfunction "SD2_28") (pintype "bidirectional"))
      (node (ref "SV4") (pin "5") (pinfunction "5_5") (pintype "passive"))
    )
    (net (code "37") (name "Net-(IC1A-SD3)") (class "Default")
      (node (ref "IC1") (pin "29") (pinfunction "SD3_29") (pintype "bidirectional"))
      (node (ref "SV4") (pin "4") (pinfunction "4_4") (pintype "passive"))
    )
    (net (code "38") (name "Net-(IC1A-SENSOR_VN)") (class "Default")
      (node (ref "IC1") (pin "8") (pinfunction "SENSOR_VN_8") (pintype "bidirectional"))
      (node (ref "SV2") (pin "4") (pinfunction "4_4") (pintype "passive"))
    )
    (net (code "39") (name "Net-(IC1A-SENSOR_VP)") (class "Default")
      (node (ref "IC1") (pin "5") (pinfunction "SENSOR_VP_5") (pintype "bidirectional"))
      (node (ref "SJ1") (pin "2") (pinfunction "2_2") (pintype "passive"))
    )
    (net (code "40") (name "Net-(IC1A-VDD_SDIO_NC)") (class "Default")
      (node (ref "C8") (pin "1") (pinfunction "1_1") (pintype "passive"))
      (node (ref "IC1") (pin "26") (pinfunction "VDD_SDIO_NC_26") (pintype "bidirectional"))
    )
    (net (code "41") (name "Net-(LED1-DI)") (class "Default")
      (node (ref "LED1") (pin "4-DIN") (pinfunction "DI_4-DIN") (pintype "input"))
      (node (ref "R6") (pin "1") (pinfunction "1_1") (pintype "passive"))
    )
    (net (code "42") (name "Net-(Q1A-B)") (class "Default")
      (node (ref "Q1") (pin "5") (pinfunction "B_5") (pintype "passive"))
      (node (ref "R9") (pin "2") (pinfunction "2_2") (pintype "passive"))
    )
    (net (code "43") (name "Net-(Q1B-B)") (class "Default")
      (node (ref "Q1") (pin "2") (pinfunction "B_2") (pintype "passive"))
      (node (ref "R10") (pin "2") (pinfunction "2_2") (pintype "passive"))
    )
    (net (code "44") (name "Net-(Q3-D)") (class "Default")
      (node (ref "Q3") (pin "3") (pinfunction "D_3") (pintype "passive"))
      (node (ref "R25") (pin "2") (pinfunction "2_2") (pintype "passive"))
      (node (ref "R27") (pin "1") (pinfunction "1_1") (pintype "passive"))
    )
    (net (code "45") (name "Net-(SJ1-Pad3)") (class "Default")
      (node (ref "SJ1") (pin "3") (pinfunction "3_3") (pintype "passive"))
      (node (ref "SV2") (pin "5") (pinfunction "5_5") (pintype "passive"))
    )
    (net (code "46") (name "Net-(U$1-2)") (class "Default")
      (node (ref "U$1") (pin "P$2") (pinfunction "2_P$2") (pintype "passive"))
      (node (ref "U$13") (pin "5") (pinfunction "L_5") (pintype "bidirectional"))
    )
    (net (code "47") (name "Net-(U$13-FB)") (class "Default")
      (node (ref "R20") (pin "2") (pinfunction "2_2") (pintype "passive"))
      (node (ref "R21") (pin "1") (pinfunction "1_1") (pintype "passive"))
      (node (ref "U$13") (pin "2") (pinfunction "FB_2") (pintype "bidirectional"))
    )
    (net (code "48") (name "Net-(U$15-FB)") (class "Default")
      (node (ref "C3") (pin "2") (pinfunction "2_2") (pintype "passive"))
      (node (ref "R39") (pin "1") (pinfunction "1_1") (pintype "passive"))
      (node (ref "R40") (pin "2") (pinfunction "2_2") (pintype "passive"))
      (node (ref "U$15") (pin "2") (pinfunction "FB_2") (pintype "bidirectional"))
    )
    (net (code "49") (name "Net-(U$15-NR{slash}SS)") (class "Default")
      (node (ref "C45") (pin "1") (pinfunction "1_1") (pintype "passive"))
      (node (ref "U$15") (pin "6") (pinfunction "NR/SS_6") (pintype "bidirectional"))
    )
    (net (code "50") (name "Net-(U1-USBDM)") (class "Default")
      (node (ref "R14") (pin "2") (pinfunction "2_2") (pintype "passive"))
      (node (ref "U1") (pin "12") (pinfunction "USBDM_12") (pintype "bidirectional"))
    )
    (net (code "51") (name "Net-(U1-USBDP)") (class "Default")
      (node (ref "R15") (pin "2") (pinfunction "2_2") (pintype "passive"))
      (node (ref "U1") (pin "11") (pinfunction "USBDP_11") (pintype "bidirectional"))
    )
    (net (code "52") (name "Net-(U3-PROG)") (class "Default")
      (node (ref "R17") (pin "2") (pinfunction "2_2") (pintype "passive"))
      (node (ref "U3") (pin "5") (pinfunction "PROG_5") (pintype "input"))
    )
    (net (code "53") (name "Net-(U3-STAT)") (class "Default")
      (node (ref "CHG2") (pin "C") (pinfunction "C_C") (pintype "passive"))
      (node (ref "U3") (pin "1") (pinfunction "STAT_1") (pintype "output"))
    )
    (net (code "54") (name "REFN0") (class "Default")
      (node (ref "TP65") (pin "TP") (pinfunction "TP_TP") (pintype "input"))
      (node (ref "U$9") (pin "8") (pinfunction "REFN0_8") (pintype "bidirectional"))
    )
    (net (code "55") (name "REFP0") (class "Default")
      (node (ref "TP58") (pin "TP") (pinfunction "TP_TP") (pintype "input"))
      (node (ref "U$9") (pin "9") (pinfunction "REFP0_9") (pintype "bidirectional"))
    )
    (net (code "56") (name "RTS") (class "Default")
      (node (ref "Q1") (pin "4") (pinfunction "E_4") (pintype "passive"))
      (node (ref "R10") (pin "1") (pinfunction "1_1") (pintype "passive"))
      (node (ref "U1") (pin "2") (pinfunction "~{RTS}_2") (pintype "bidirectional"))
    )
    (net (code "57") (name "RXD") (class "Default")
      (node (ref "R13") (pin "2") (pinfunction "2_2") (pintype "passive"))
      (node (ref "U1") (pin "4") (pinfunction "RXD_4") (pintype "bidirectional"))
    )
    (net (code "58") (name "SCL") (class "Default")
      (node (ref "IC1") (pin "39") (pinfunction "IO22_39") (pintype "bidirectional"))
      (node (ref "J4") (pin "4") (pinfunction "4_4") (pintype "passive"))
      (node (ref "R3") (pin "1") (pinfunction "1_1") (pintype "passive"))
    )
    (net (code "59") (name "SCL1") (class "Default")
      (node (ref "IC1") (pin "14") (pinfunction "IO25_14") (pintype "bidirectional"))
      (node (ref "J1") (pin "4") (pinfunction "4_4") (pintype "passive"))
      (node (ref "R18") (pin "1") (pinfunction "1_1") (pintype "passive"))
    )
    (net (code "60") (name "SCLK") (class "Default")
      (node (ref "IC1") (pin "35") (pinfunction "IO18_35") (pintype "bidirectional"))
      (node (ref "U$20") (pin "5") (pinfunction "CLK_5") (pintype "bidirectional"))
      (node (ref "U$9") (pin "1") (pinfunction "SCLK_1") (pintype "bidirectional"))
    )
    (net (code "61") (name "SDA") (class "Default")
      (node (ref "IC1") (pin "42") (pinfunction "IO21_42") (pintype "power_in"))
      (node (ref "J4") (pin "3") (pinfunction "3_3") (pintype "passive"))
      (node (ref "R4") (pin "1") (pinfunction "1_1") (pintype "passive"))
    )
    (net (code "62") (name "SDA1") (class "Default")
      (node (ref "IC1") (pin "15") (pinfunction "IO26_15") (pintype "bidirectional"))
      (node (ref "J1") (pin "3") (pinfunction "3_3") (pintype "passive"))
      (node (ref "R5") (pin "1") (pinfunction "1_1") (pintype "passive"))
    )
    (net (code "63") (name "SENSOR_CAPN") (class "Default")
      (node (ref "IC1") (pin "7") (pinfunction "SENSOR_CAPN_7") (pintype "power_in"))
    )
    (net (code "64") (name "TXD") (class "Default")
      (node (ref "R12") (pin "2") (pinfunction "2_2") (pintype "passive"))
      (node (ref "U1") (pin "20") (pinfunction "TXD_20") (pintype "bidirectional"))
    )
    (net (code "65") (name "U0RXD") (class "Default")
      (node (ref "IC1") (pin "40") (pinfunction "U0RXD_40") (pintype "bidirectional"))
      (node (ref "R12") (pin "1") (pinfunction "1_1") (pintype "passive"))
    )
    (net (code "66") (name "U0TXD") (class "Default")
      (node (ref "IC1") (pin "41") (pinfunction "U0TXD_41") (pintype "bidirectional"))
      (node (ref "R13") (pin "1") (pinfunction "1_1") (pintype "passive"))
    )
    (net (code "67") (name "VBAT") (class "Default")
      (node (ref "C65") (pin "1") (pinfunction "1_1") (pintype "passive"))
      (node (ref "JP6") (pin "2") (pinfunction "2_2") (pintype "passive"))
      (node (ref "Q2") (pin "3") (pinfunction "D_3") (pintype "passive"))
      (node (ref "Q3") (pin "2") (pinfunction "S_2") (pintype "passive"))
      (node (ref "R27") (pin "2") (pinfunction "2_2") (pintype "passive"))
      (node (ref "R7") (pin "2") (pinfunction "2_2") (pintype "passive"))
      (node (ref "U3") (pin "3") (pinfunction "VBAT_3") (pintype "power_in"))
    )
    (net (code "68") (name "VCC") (class "Default")
      (node (ref "C44") (pin "1") (pinfunction "1_1") (pintype "passive"))
      (node (ref "C83") (pin "1") (pinfunction "1_1") (pintype "passive"))
      (node (ref "R20") (pin "1") (pinfunction "1_1") (pintype "passive"))
      (node (ref "TP41") (pin "TP") (pinfunction "TP_TP") (pintype "input"))
      (node (ref "U$13") (pin "4") (pinfunction "VOUT_4") (pintype "bidirectional"))
      (node (ref "U$15") (pin "5") (pinfunction "EN_5") (pintype "bidirectional"))
      (node (ref "U$15") (pin "8") (pinfunction "IN_8") (pintype "bidirectional"))
    )
    (net (code "69") (name "VIN") (class "Default")
      (node (ref "C1") (pin "1") (pinfunction "1_1") (pintype "passive"))
      (node (ref "C63") (pin "1") (pinfunction "1_1") (pintype "passive"))
      (node (ref "C72") (pin "2") (pinfunction "2_2") (pintype "passive"))
      (node (ref "D1") (pin "C") (pinfunction "C_C") (pintype "passive"))
      (node (ref "Q2") (pin "2") (pinfunction "S_2") (pintype "passive"))
      (node (ref "S2") (pin "3") (pinfunction "S_3") (pintype "passive"))
      (node (ref "U$1") (pin "P$1") (pinfunction "1_P$1") (pintype "passive"))
      (node (ref "U$13") (pin "1") (pinfunction "VIN_1") (pintype "bidirectional"))
      (node (ref "U8") (pin "1") (pinfunction "IN_1") (pintype "input"))
    )
    (net (code "70") (name "VUSB") (class "Default")
      (node (ref "C60") (pin "1") (pinfunction "1_1") (pintype "passive"))
      (node (ref "C61") (pin "1") (pinfunction "1_1") (pintype "passive"))
      (node (ref "C64") (pin "1") (pinfunction "1_1") (pintype "passive"))
      (node (ref "D1") (pin "A") (pinfunction "A_A") (pintype "passive"))
      (node (ref "JP7") (pin "1") (pinfunction "VCC_1") (pintype "bidirectional"))
      (node (ref "Q2") (pin "1") (pinfunction "G_1") (pintype "passive"))
      (node (ref "R16") (pin "1") (pinfunction "1_1") (pintype "passive"))
      (node (ref "R23") (pin "2") (pinfunction "2_2") (pintype "passive"))
      (node (ref "U1") (pin "15") (pinfunction "VCC_15") (pintype "bidirectional"))
      (node (ref "U3") (pin "4") (pinfunction "VIN_4") (pintype "power_in"))
    )
    (net (code "71") (name "WS2812") (class "Default")
      (node (ref "IC1") (pin "17") (pinfunction "IO14_17") (pintype "bidirectional"))
      (node (ref "R6") (pin "2") (pinfunction "2_2") (pintype "passive"))
    )
    (net (code "72") (name "unconnected-(IC1A-CAP1_NC-Pad48)") (class "Default")
      (node (ref "IC1") (pin "48") (pinfunction "CAP1_NC_48") (pintype "bidirectional"))
    )
    (net (code "73") (name "unconnected-(IC1A-CAP2_NC-Pad47)") (class "Default")
      (node (ref "IC1") (pin "47") (pinfunction "CAP2_NC_47") (pintype "bidirectional"))
    )
    (net (code "74") (name "unconnected-(IC1A-IO2-Pad22)") (class "Default")
      (node (ref "IC1") (pin "22") (pinfunction "IO2_22") (pintype "bidirectional"))
    )
    (net (code "75") (name "unconnected-(IC1A-IO5-Pad34)") (class "Default")
      (node (ref "IC1") (pin "34") (pinfunction "IO5_34") (pintype "bidirectional"))
    )
    (net (code "76") (name "unconnected-(IC1A-IO35-Pad11)") (class "Default")
      (node (ref "IC1") (pin "11") (pinfunction "IO35_11") (pintype "bidirectional"))
    )
    (net (code "77") (name "unconnected-(IC1A-SD0-Pad32)") (class "Default")
      (node (ref "IC1") (pin "32") (pinfunction "SD0_32") (pintype "bidirectional"))
    )
    (net (code "78") (name "unconnected-(IC1A-SD1-Pad33)") (class "Default")
      (node (ref "IC1") (pin "33") (pinfunction "SD1_33") (pintype "bidirectional"))
    )
    (net (code "79") (name "unconnected-(IC1A-SENSOR_CAPP-Pad6)") (class "Default")
      (node (ref "IC1") (pin "6") (pinfunction "SENSOR_CAPP_6") (pintype "bidirectional"))
    )
    (net (code "80") (name "unconnected-(IC1A-XTAL_N_NC-Pad44)") (class "Default")
      (node (ref "IC1") (pin "44") (pinfunction "XTAL_N_NC_44") (pintype "bidirectional"))
    )
    (net (code "81") (name "unconnected-(IC1A-XTAL_P_NC-Pad45)") (class "Default")
      (node (ref "IC1") (pin "45") (pinfunction "XTAL_P_NC_45") (pintype "bidirectional"))
    )
    (net (code "82") (name "unconnected-(JP7-ID-Pad4)") (class "Default")
      (node (ref "JP7") (pin "4") (pinfunction "ID_4") (pintype "bidirectional"))
    )
    (net (code "83") (name "unconnected-(LED1-DO-Pad2-DOUT)") (class "Default")
      (node (ref "LED1") (pin "2-DOUT") (pinfunction "DO_2-DOUT") (pintype "output"))
    )
    (net (code "84") (name "unconnected-(SW2-P1-PadA')") (class "Default")
      (node (ref "SW2") (pin "A'") (pinfunction "P1_A'") (pintype "passive"))
    )
    (net (code "85") (name "unconnected-(U$20-DATA1-Pad8)") (class "Default")
      (node (ref "U$20") (pin "8") (pinfunction "DATA1_8") (pintype "bidirectional"))
    )
    (net (code "86") (name "unconnected-(U$20-DATA2-Pad1)") (class "Default")
      (node (ref "U$20") (pin "1") (pinfunction "DATA2_1") (pintype "bidirectional"))
    )
    (net (code "87") (name "unconnected-(U$20-DET-Pad9)") (class "Default")
      (node (ref "U$20") (pin "9") (pinfunction "DET_9") (pintype "bidirectional"))
    )
    (net (code "88") (name "unconnected-(U1-CBUS0-Pad18)") (class "Default")
      (node (ref "U1") (pin "18") (pinfunction "CBUS0_18") (pintype "bidirectional"))
    )
    (net (code "89") (name "unconnected-(U1-CBUS1-Pad17)") (class "Default")
      (node (ref "U1") (pin "17") (pinfunction "CBUS1_17") (pintype "bidirectional"))
    )
    (net (code "90") (name "unconnected-(U1-CBUS2-Pad10)") (class "Default")
      (node (ref "U1") (pin "10") (pinfunction "CBUS2_10") (pintype "bidirectional"))
    )
    (net (code "91") (name "unconnected-(U1-CBUS3-Pad19)") (class "Default")
      (node (ref "U1") (pin "19") (pinfunction "CBUS3_19") (pintype "bidirectional"))
    )
    (net (code "92") (name "unconnected-(U1-~{CTS}-Pad9)") (class "Default")
      (node (ref "U1") (pin "9") (pinfunction "~{CTS}_9") (pintype "bidirectional"))
    )
    (net (code "93") (name "unconnected-(U1-~{DCD}-Pad8)") (class "Default")
      (node (ref "U1") (pin "8") (pinfunction "~{DCD}_8") (pintype "bidirectional"))
    )
    (net (code "94") (name "unconnected-(U1-~{DSR}-Pad7)") (class "Default")
      (node (ref "U1") (pin "7") (pinfunction "~{DSR}_7") (pintype "bidirectional"))
    )
    (net (code "95") (name "unconnected-(U1-~{RI}-Pad5)") (class "Default")
      (node (ref "U1") (pin "5") (pinfunction "~{RI}_5") (pintype "bidirectional"))
    )
    (net (code "96") (name "unconnected-(U8-BP-Pad4)") (class "Default")
      (node (ref "U8") (pin "4") (pinfunction "BP_4") (pintype "input"))
    )
    (net (code "97") (name "~{CS1}") (class "Default")
      (node (ref "R29") (pin "1") (pinfunction "1_1") (pintype "passive"))
      (node (ref "U$9") (pin "2") (pinfunction "~{CS}_2") (pintype "bidirectional"))
    )
    (net (code "98") (name "~{DRDY}") (class "Default")
      (node (ref "IC1") (pin "10") (pinfunction "IO34_10") (pintype "bidirectional"))
      (node (ref "U$9") (pin "14") (pinfunction "~{DRDY}_14") (pintype "bidirectional"))
    )
  )
)
